# untitled.net
KiCad netlist of a schematic drawn in EAGLE
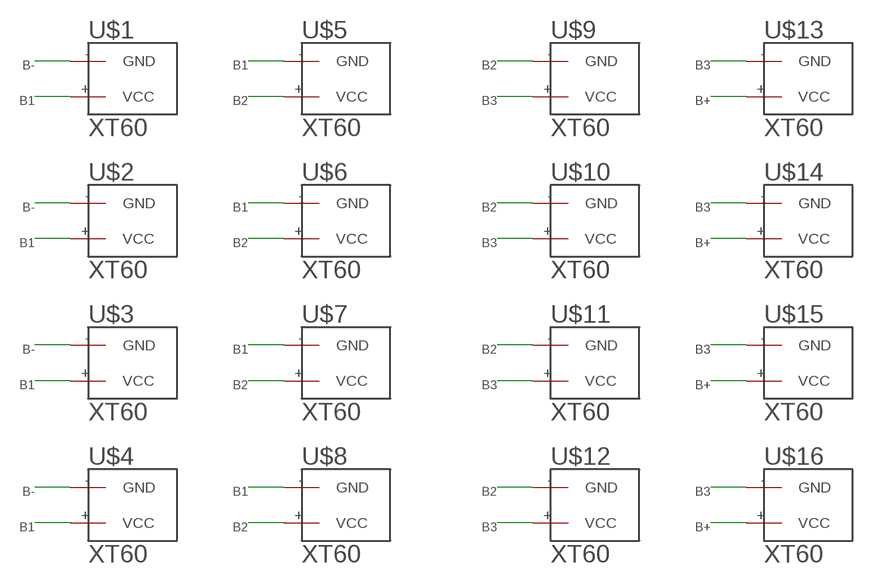
[diagram p0: schematic, sheet 1]

(export (version "E")
  (design (tool "Eeschema 10.0.6"))
  (components
    (comp (ref "U$1")
      (value "XT60")
      (footprint "eagle-import:XT60")
      (libsource (lib "eagle-import") (part "XT60"))
    )
    (comp (ref "U$2")
      (value "XT60")
      (footprint "eagle-import:XT60")
      (libsource (lib "eagle-import") (part "XT60"))
    )
    (comp (ref "U$3")
      (value "XT60")
      (footprint "eagle-import:XT60")
      (libsource (lib "eagle-import") (part "XT60"))
    )
    (comp (ref "U$4")
      (value "XT60")
      (footprint "eagle-import:XT60")
      (libsource (lib "eagle-import") (part "XT60"))
    )
    (comp (ref "U$5")
      (value "XT60")
      (footprint "eagle-import:XT60")
      (libsource (lib "eagle-import") (part "XT60"))
    )
    (comp (ref "U$6")
      (value "XT60")
      (footprint "eagle-import:XT60")
      (libsource (lib "eagle-import") (part "XT60"))
    )
    (comp (ref "U$7")
      (value "XT60")
      (footprint "eagle-import:XT60")
      (libsource (lib "eagle-import") (part "XT60"))
    )
    (comp (ref "U$8")
      (value "XT60")
      (footprint "eagle-import:XT60")
      (libsource (lib "eagle-import") (part "XT60"))
    )
    (comp (ref "U$9")
      (value "XT60")
      (footprint "eagle-import:XT60")
      (libsource (lib "eagle-import") (part "XT60"))
    )
    (comp (ref "U$10")
      (value "XT60")
      (footprint "eagle-import:XT60")
      (libsource (lib "eagle-import") (part "XT60"))
    )
    (comp (ref "U$11")
      (value "XT60")
      (footprint "eagle-import:XT60")
      (libsource (lib "eagle-import") (part "XT60"))
    )
    (comp (ref "U$12")
      (value "XT60")
      (footprint "eagle-import:XT60")
      (libsource (lib "eagle-import") (part "XT60"))
    )
    (comp (ref "U$13")
      (value "XT60")
      (footprint "eagle-import:XT60")
      (libsource (lib "eagle-import") (part "XT60"))
    )
    (comp (ref "U$14")
      (value "XT60")
      (footprint "eagle-import:XT60")
      (libsource (lib "eagle-import") (part "XT60"))
    )
    (comp (ref "U$15")
      (value "XT60")
      (footprint "eagle-import:XT60")
      (libsource (lib "eagle-import") (part "XT60"))
    )
    (comp (ref "U$16")
      (value "XT60")
      (footprint "eagle-import:XT60")
      (libsource (lib "eagle-import") (part "XT60"))
    )
  )
  (nets
    (net (code "1") (name "B+") (class "Default")
      (node (ref "U$13") (pin "+") (pinfunction "VCC_+") (pintype "bidirectional"))
      (node (ref "U$14") (pin "+") (pinfunction "VCC_+") (pintype "bidirectional"))
      (node (ref "U$15") (pin "+") (pinfunction "VCC_+") (pintype "bidirectional"))
      (node (ref "U$16") (pin "+") (pinfunction "VCC_+") (pintype "bidirectional"))
    )
    (net (code "2") (name "B-") (class "Default")
      (node (ref "U$1") (pin "-") (pinfunction "GND_-") (pintype "bidirectional"))
      (node (ref "U$2") (pin "-") (pinfunction "GND_-") (pintype "bidirectional"))
      (node (ref "U$3") (pin "-") (pinfunction "GND_-") (pintype "bidirectional"))
      (node (ref "U$4") (pin "-") (pinfunction "GND_-") (pintype "bidirectional"))
    )
    (net (code "3") (name "B1") (class "Default")
      (node (ref "U$1") (pin "+") (pinfunction "VCC_+") (pintype "bidirectional"))
      (node (ref "U$2") (pin "+") (pinfunction "VCC_+") (pintype "bidirectional"))
      (node (ref "U$3") (pin "+") (pinfunction "VCC_+") (pintype "bidirectional"))
      (node (ref "U$4") (pin "+") (pinfunction "VCC_+") (pintype "bidirectional"))
      (node (ref "U$5") (pin "-") (pinfunction "GND_-") (pintype "bidirectional"))
      (node (ref "U$6") (pin "-") (pinfunction "GND_-") (pintype "bidirectional"))
      (node (ref "U$7") (pin "-") (pinfunction "GND_-") (pintype "bidirectional"))
      (node (ref "U$8") (pin "-") (pinfunction "GND_-") (pintype "bidirectional"))
    )
    (net (code "4") (name "B2") (class "Default")
      (node (ref "U$10") (pin "-") (pinfunction "GND_-") (pintype "bidirectional"))
      (node (ref "U$11") (pin "-") (pinfunction "GND_-") (pintype "bidirectional"))
      (node (ref "U$12") (pin "-") (pinfunction "GND_-") (pintype "bidirectional"))
      (node (ref "U$5") (pin "+") (pinfunction "VCC_+") (pintype "bidirectional"))
      (node (ref "U$6") (pin "+") (pinfunction "VCC_+") (pintype "bidirectional"))
      (node (ref "U$7") (pin "+") (pinfunction "VCC_+") (pintype "bidirectional"))
      (node (ref "U$8") (pin "+") (pinfunction "VCC_+") (pintype "bidirectional"))
      (node (ref "U$9") (pin "-") (pinfunction "GND_-") (pintype "bidirectional"))
    )
    (net (code "5") (name "B3") (class "Default")
      (node (ref "U$10") (pin "+") (pinfunction "VCC_+") (pintype "bidirectional"))
      (node (ref "U$11") (pin "+") (pinfunction "VCC_+") (pintype "bidirectional"))
      (node (ref "U$12") (pin "+") (pinfunction "VCC_+") (pintype "bidirectional"))
      (node (ref "U$13") (pin "-") (pinfunction "GND_-") (pintype "bidirectional"))
      (node (ref "U$14") (pin "-") (pinfunction "GND_-") (pintype "bidirectional"))
      (node (ref "U$15") (pin "-") (pinfunction "GND_-") (pintype "bidirectional"))
      (node (ref "U$16") (pin "-") (pinfunction "GND_-") (pintype "bidirectional"))
      (node (ref "U$9") (pin "+") (pinfunction "VCC_+") (pintype "bidirectional"))
    )
  )
)
